# TPS54260.net
KiCad netlist of a schematic drawn in Altium Designer
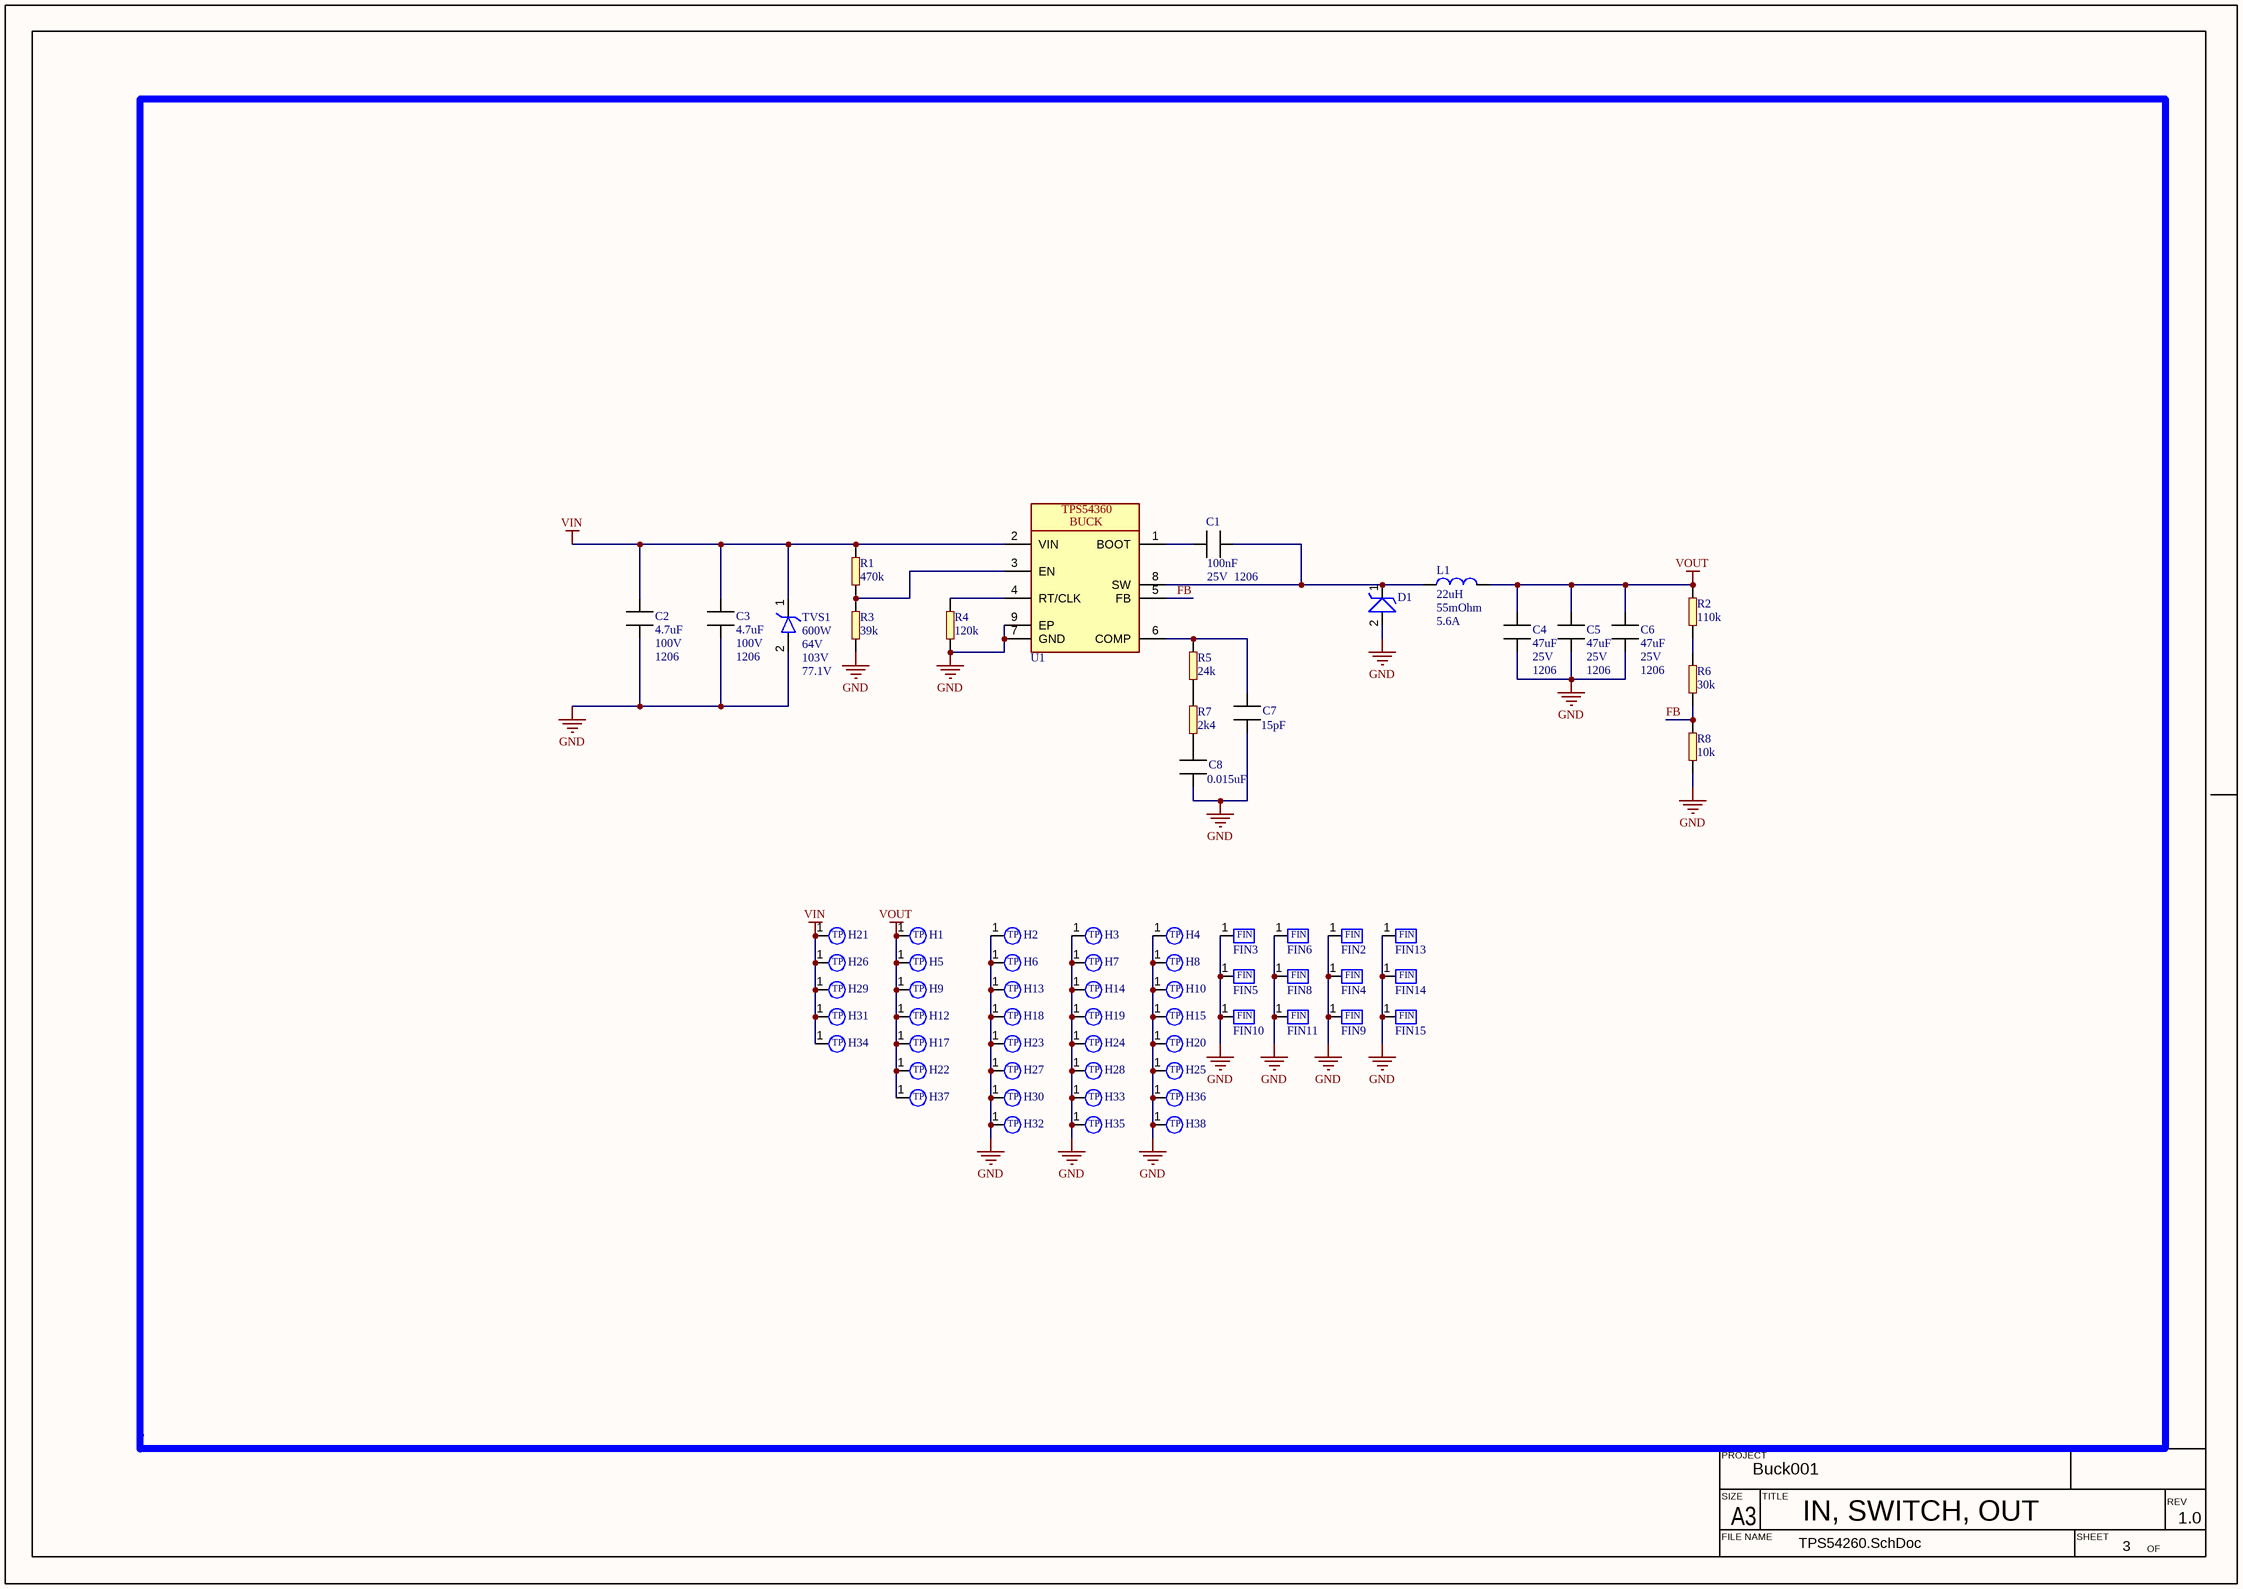
[diagram p0: TPS54260.SchDoc]

(export (version "E")
  (design (tool "Eeschema 10.0.6"))
  (components
    (comp (ref "C1")
      (value "100nF")
      (footprint "CAP1206")
      (description "MLCC 1206 (3216 Metric)")
      (fields
        (field (name "VOLTAGE") "25V")
        (field (name "PACKAGE") "1206")
        (field (name "Comment") "MLCC_1206")
      )
      (libsource (lib "Capacitor") (part "MLCC_1206"))
    )
    (comp (ref "C2")
      (value "4.7uF")
      (footprint "CAP1206")
      (description "MLCC 1206 (3216 Metric)")
      (fields
        (field (name "VOLTAGE") "100V")
        (field (name "PACKAGE") "1206")
        (field (name "Comment") "MLCC_1206")
      )
      (libsource (lib "Capacitor") (part "MLCC_1206"))
    )
    (comp (ref "C3")
      (value "4.7uF")
      (footprint "CAP1206")
      (description "MLCC 1206 (3216 Metric)")
      (fields
        (field (name "VOLTAGE") "100V")
        (field (name "PACKAGE") "1206")
        (field (name "Comment") "MLCC_1206")
      )
      (libsource (lib "Capacitor") (part "MLCC_1206"))
    )
    (comp (ref "C4")
      (value "47uF")
      (footprint "CAP1206")
      (description "MLCC 1206 (3216 Metric)")
      (fields
        (field (name "VOLTAGE") "25V")
        (field (name "PACKAGE") "1206")
        (field (name "Comment") "MLCC_1206")
      )
      (libsource (lib "Capacitor") (part "MLCC_1206"))
    )
    (comp (ref "C5")
      (value "47uF")
      (footprint "CAP1206")
      (description "MLCC 1206 (3216 Metric)")
      (fields
        (field (name "VOLTAGE") "25V")
        (field (name "PACKAGE") "1206")
        (field (name "Comment") "MLCC_1206")
      )
      (libsource (lib "Capacitor") (part "MLCC_1206"))
    )
    (comp (ref "C6")
      (value "47uF")
      (footprint "CAP1206")
      (description "MLCC 1206 (3216 Metric)")
      (fields
        (field (name "VOLTAGE") "25V")
        (field (name "PACKAGE") "1206")
        (field (name "Comment") "MLCC_1206")
      )
      (libsource (lib "Capacitor") (part "MLCC_1206"))
    )
    (comp (ref "C7")
      (value "15pF")
      (footprint "CAPC1608X10N")
      (description "Chip Capacitor, 2-Leads, Body 1.60x0.80mm, IPC Medium Density")
      (fields (field (name "Comment") "ERP_102-1"))
      (libsource (lib "Capacitor") (part "MLCC_0603"))
    )
    (comp (ref "C8")
      (value "0.015uF")
      (footprint "CAPC1608X10N")
      (description "Chip Capacitor, 2-Leads, Body 1.60x0.80mm, IPC Medium Density")
      (fields (field (name "Comment") "ERP_102-1"))
      (libsource (lib "Capacitor") (part "MLCC_0603"))
    )
    (comp (ref "D1")
      (value "CDBB_5XX_HF")
      (footprint "SMB(DO214AA)")
      (description "SMB(DO-214AA) DIODE HF 5A")
      (libsource (lib "Schottky") (part "CDBB_5XX_HF"))
    )
    (comp (ref "FIN2")
      (value "FIN_5X1")
      (footprint "FIN_5X1")
      (description "FIN_5X1 Radiator")
      (libsource (lib "Jumper") (part "FIN_5X1"))
    )
    (comp (ref "FIN3")
      (value "FIN_5X1")
      (footprint "FIN_5X1")
      (description "FIN_5X1 Radiator")
      (libsource (lib "Jumper") (part "FIN_5X1"))
    )
    (comp (ref "FIN4")
      (value "FIN_5X1")
      (footprint "FIN_5X1")
      (description "FIN_5X1 Radiator")
      (libsource (lib "Jumper") (part "FIN_5X1"))
    )
    (comp (ref "FIN5")
      (value "FIN_5X1")
      (footprint "FIN_5X1")
      (description "FIN_5X1 Radiator")
      (libsource (lib "Jumper") (part "FIN_5X1"))
    )
    (comp (ref "FIN6")
      (value "FIN_5X1")
      (footprint "FIN_5X1")
      (description "FIN_5X1 Radiator")
      (libsource (lib "Jumper") (part "FIN_5X1"))
    )
    (comp (ref "FIN8")
      (value "FIN_5X1")
      (footprint "FIN_5X1")
      (description "FIN_5X1 Radiator")
      (libsource (lib "Jumper") (part "FIN_5X1"))
    )
    (comp (ref "FIN9")
      (value "FIN_5X1")
      (footprint "FIN_5X1")
      (description "FIN_5X1 Radiator")
      (libsource (lib "Jumper") (part "FIN_5X1"))
    )
    (comp (ref "FIN10")
      (value "FIN_5X1")
      (footprint "FIN_5X1")
      (description "FIN_5X1 Radiator")
      (libsource (lib "Jumper") (part "FIN_5X1"))
    )
    (comp (ref "FIN11")
      (value "FIN_5X1")
      (footprint "FIN_5X1")
      (description "FIN_5X1 Radiator")
      (libsource (lib "Jumper") (part "FIN_5X1"))
    )
    (comp (ref "FIN13")
      (value "FIN_5X1")
      (footprint "FIN_5X1")
      (description "FIN_5X1 Radiator")
      (libsource (lib "Jumper") (part "FIN_5X1"))
    )
    (comp (ref "FIN14")
      (value "FIN_5X1")
      (footprint "FIN_5X1")
      (description "FIN_5X1 Radiator")
      (libsource (lib "Jumper") (part "FIN_5X1"))
    )
    (comp (ref "FIN15")
      (value "FIN_5X1")
      (footprint "FIN_5X1")
      (description "FIN_5X1 Radiator")
      (libsource (lib "Jumper") (part "FIN_5X1"))
    )
    (comp (ref "H1")
      (value "Castalated_Hole_1MM")
      (footprint "CS_1MM")
      (libsource (lib "Jumper") (part "Castalated_Hole_1MM"))
    )
    (comp (ref "H2")
      (value "Castalated_Hole_1MM")
      (footprint "CS_1MM")
      (libsource (lib "Jumper") (part "Castalated_Hole_1MM"))
    )
    (comp (ref "H3")
      (value "Castalated_Hole_1MM")
      (footprint "CS_1MM")
      (libsource (lib "Jumper") (part "Castalated_Hole_1MM"))
    )
    (comp (ref "H4")
      (value "Castalated_Hole_1MM")
      (footprint "CS_1MM")
      (libsource (lib "Jumper") (part "Castalated_Hole_1MM"))
    )
    (comp (ref "H5")
      (value "Castalated_Hole_1MM")
      (footprint "CS_1MM")
      (libsource (lib "Jumper") (part "Castalated_Hole_1MM"))
    )
    (comp (ref "H6")
      (value "Castalated_Hole_1MM")
      (footprint "CS_1MM")
      (libsource (lib "Jumper") (part "Castalated_Hole_1MM"))
    )
    (comp (ref "H7")
      (value "Castalated_Hole_1MM")
      (footprint "CS_1MM")
      (libsource (lib "Jumper") (part "Castalated_Hole_1MM"))
    )
    (comp (ref "H8")
      (value "Castalated_Hole_1MM")
      (footprint "CS_1MM")
      (libsource (lib "Jumper") (part "Castalated_Hole_1MM"))
    )
    (comp (ref "H9")
      (value "Castalated_Hole_1MM")
      (footprint "CS_1MM")
      (libsource (lib "Jumper") (part "Castalated_Hole_1MM"))
    )
    (comp (ref "H10")
      (value "Castalated_Hole_1MM")
      (footprint "CS_1MM")
      (libsource (lib "Jumper") (part "Castalated_Hole_1MM"))
    )
    (comp (ref "H12")
      (value "Castalated_Hole_1MM")
      (footprint "CS_1MM")
      (libsource (lib "Jumper") (part "Castalated_Hole_1MM"))
    )
    (comp (ref "H13")
      (value "Castalated_Hole_1MM")
      (footprint "CS_1MM")
      (libsource (lib "Jumper") (part "Castalated_Hole_1MM"))
    )
    (comp (ref "H14")
      (value "Castalated_Hole_1MM")
      (footprint "CS_1MM")
      (libsource (lib "Jumper") (part "Castalated_Hole_1MM"))
    )
    (comp (ref "H15")
      (value "Castalated_Hole_1MM")
      (footprint "CS_1MM")
      (libsource (lib "Jumper") (part "Castalated_Hole_1MM"))
    )
    (comp (ref "H17")
      (value "Castalated_Hole_1MM")
      (footprint "CS_1MM")
      (libsource (lib "Jumper") (part "Castalated_Hole_1MM"))
    )
    (comp (ref "H18")
      (value "Castalated_Hole_1MM")
      (footprint "CS_1MM")
      (libsource (lib "Jumper") (part "Castalated_Hole_1MM"))
    )
    (comp (ref "H19")
      (value "Castalated_Hole_1MM")
      (footprint "CS_1MM")
      (libsource (lib "Jumper") (part "Castalated_Hole_1MM"))
    )
    (comp (ref "H20")
      (value "Castalated_Hole_1MM")
      (footprint "CS_1MM")
      (libsource (lib "Jumper") (part "Castalated_Hole_1MM"))
    )
    (comp (ref "H21")
      (value "Castalated_Hole_1MM")
      (footprint "CS_1MM")
      (libsource (lib "Jumper") (part "Castalated_Hole_1MM"))
    )
    (comp (ref "H22")
      (value "Castalated_Hole_1MM")
      (footprint "CS_1MM")
      (libsource (lib "Jumper") (part "Castalated_Hole_1MM"))
    )
    (comp (ref "H23")
      (value "Castalated_Hole_1MM")
      (footprint "CS_1MM")
      (libsource (lib "Jumper") (part "Castalated_Hole_1MM"))
    )
    (comp (ref "H24")
      (value "Castalated_Hole_1MM")
      (footprint "CS_1MM")
      (libsource (lib "Jumper") (part "Castalated_Hole_1MM"))
    )
    (comp (ref "H25")
      (value "Castalated_Hole_1MM")
      (footprint "CS_1MM")
      (libsource (lib "Jumper") (part "Castalated_Hole_1MM"))
    )
    (comp (ref "H26")
      (value "Castalated_Hole_1MM")
      (footprint "CS_1MM")
      (libsource (lib "Jumper") (part "Castalated_Hole_1MM"))
    )
    (comp (ref "H27")
      (value "Castalated_Hole_1MM")
      (footprint "CS_1MM")
      (libsource (lib "Jumper") (part "Castalated_Hole_1MM"))
    )
    (comp (ref "H28")
      (value "Castalated_Hole_1MM")
      (footprint "CS_1MM")
      (libsource (lib "Jumper") (part "Castalated_Hole_1MM"))
    )
    (comp (ref "H29")
      (value "Castalated_Hole_1MM")
      (footprint "CS_1MM")
      (libsource (lib "Jumper") (part "Castalated_Hole_1MM"))
    )
    (comp (ref "H30")
      (value "Castalated_Hole_1MM")
      (footprint "CS_1MM")
      (libsource (lib "Jumper") (part "Castalated_Hole_1MM"))
    )
    (comp (ref "H31")
      (value "Castalated_Hole_1MM")
      (footprint "CS_1MM")
      (libsource (lib "Jumper") (part "Castalated_Hole_1MM"))
    )
    (comp (ref "H32")
      (value "Castalated_Hole_1MM")
      (footprint "CS_1MM")
      (libsource (lib "Jumper") (part "Castalated_Hole_1MM"))
    )
    (comp (ref "H33")
      (value "Castalated_Hole_1MM")
      (footprint "CS_1MM")
      (libsource (lib "Jumper") (part "Castalated_Hole_1MM"))
    )
    (comp (ref "H34")
      (value "Castalated_Hole_1MM")
      (footprint "CS_1MM")
      (libsource (lib "Jumper") (part "Castalated_Hole_1MM"))
    )
    (comp (ref "H35")
      (value "Castalated_Hole_1MM")
      (footprint "CS_1MM")
      (libsource (lib "Jumper") (part "Castalated_Hole_1MM"))
    )
    (comp (ref "H36")
      (value "Castalated_Hole_1MM")
      (footprint "CS_1MM")
      (libsource (lib "Jumper") (part "Castalated_Hole_1MM"))
    )
    (comp (ref "H37")
      (value "Castalated_Hole_1MM")
      (footprint "CS_1MM")
      (libsource (lib "Jumper") (part "Castalated_Hole_1MM"))
    )
    (comp (ref "H38")
      (value "Castalated_Hole_1MM")
      (footprint "CS_1MM")
      (libsource (lib "Jumper") (part "Castalated_Hole_1MM"))
    )
    (comp (ref "L1")
      (value "22uH")
      (footprint "SRP6060FA")
      (description "SRP6060FA Bourns 6.4 x 6.6 MM")
      (fields (field (name "DCR") "55mOhm") (field (name "ISAT") "5.6A") (field (name "Comment") "SRP6060FA"))
      (libsource (lib "Inductor") (part "SRP6060FA"))
    )
    (comp (ref "R1")
      (value "470k")
      (footprint "RES_0603")
      (description "RES_0603")
      (fields (field (name "Comment") "ERP_101-1"))
      (libsource (lib "Resistor") (part "RES_0603"))
    )
    (comp (ref "R2")
      (value "110k")
      (footprint "RES_0603")
      (description "RES_0603")
      (fields (field (name "Comment") "ERP_101-1"))
      (libsource (lib "Resistor") (part "RES_0603"))
    )
    (comp (ref "R3")
      (value "39k")
      (footprint "RES_0603")
      (description "RES_0603")
      (fields (field (name "Comment") "ERP_101-1"))
      (libsource (lib "Resistor") (part "RES_0603"))
    )
    (comp (ref "R4")
      (value "120k")
      (footprint "RES_0603")
      (description "RES_0603")
      (fields (field (name "Comment") "ERP_101-1"))
      (libsource (lib "Resistor") (part "RES_0603"))
    )
    (comp (ref "R5")
      (value "24k")
      (footprint "RES_0603")
      (description "RES_0603")
      (fields (field (name "Comment") "ERP_101-1"))
      (libsource (lib "Resistor") (part "RES_0603"))
    )
    (comp (ref "R6")
      (value "30k")
      (footprint "RES_0603")
      (description "RES_0603")
      (fields (field (name "Comment") "ERP_101-1"))
      (libsource (lib "Resistor") (part "RES_0603"))
    )
    (comp (ref "R7")
      (value "2k4")
      (footprint "RES_0603")
      (description "RES_0603")
      (fields (field (name "Comment") "ERP_101-1"))
      (libsource (lib "Resistor") (part "RES_0603"))
    )
    (comp (ref "R8")
      (value "10k")
      (footprint "RES_0603")
      (description "RES_0603")
      (fields (field (name "Comment") "ERP_101-1"))
      (libsource (lib "Resistor") (part "RES_0603"))
    )
    (comp (ref "TVS1")
      (value "SMBJ58A")
      (footprint "SMBJ58A")
      (description "TVS DIODE DO-214AA, SMB")
      (fields
        (field (name "PD") "600W")
        (field (name "VRV") "64V")
        (field (name "VCL") "103V")
        (field (name "VBR") "77.1V")
      )
      (libsource (lib "TVS") (part "SMBJ58A"))
    )
    (comp (ref "U1")
      (value "TPS54360DDAR")
      (footprint "TPS54360DDAR")
      (libsource (lib "DCDC_Switcher") (part "TPS54360DDAR"))
    )
  )
  (nets
    (net (code "1") (name "/FB") (class "Default")
      (node (ref "R6") (pin "1") (pinfunction "1_1") (pintype "passive"))
      (node (ref "R8") (pin "2") (pinfunction "2_2") (pintype "passive"))
      (node (ref "U1") (pin "5") (pinfunction "FB_5") (pintype "passive"))
    )
    (net (code "2") (name "GND") (class "Default")
      (node (ref "C2") (pin "2") (pinfunction "2_2") (pintype "passive"))
      (node (ref "C3") (pin "2") (pinfunction "2_2") (pintype "passive"))
      (node (ref "C4") (pin "2") (pinfunction "2_2") (pintype "passive"))
      (node (ref "C5") (pin "2") (pinfunction "2_2") (pintype "passive"))
      (node (ref "C6") (pin "2") (pinfunction "2_2") (pintype "passive"))
      (node (ref "C7") (pin "2") (pinfunction "2_2") (pintype "passive"))
      (node (ref "C8") (pin "2") (pinfunction "2_2") (pintype "passive"))
      (node (ref "D1") (pin "2") (pinfunction "A_2") (pintype "passive"))
      (node (ref "FIN10") (pin "1") (pinfunction "1_1") (pintype "passive"))
      (node (ref "FIN11") (pin "1") (pinfunction "1_1") (pintype "passive"))
      (node (ref "FIN13") (pin "1") (pinfunction "1_1") (pintype "passive"))
      (node (ref "FIN14") (pin "1") (pinfunction "1_1") (pintype "passive"))
      (node (ref "FIN15") (pin "1") (pinfunction "1_1") (pintype "passive"))
      (node (ref "FIN2") (pin "1") (pinfunction "1_1") (pintype "passive"))
      (node (ref "FIN3") (pin "1") (pinfunction "1_1") (pintype "passive"))
      (node (ref "FIN4") (pin "1") (pinfunction "1_1") (pintype "passive"))
      (node (ref "FIN5") (pin "1") (pinfunction "1_1") (pintype "passive"))
      (node (ref "FIN6") (pin "1") (pinfunction "1_1") (pintype "passive"))
      (node (ref "FIN8") (pin "1") (pinfunction "1_1") (pintype "passive"))
      (node (ref "FIN9") (pin "1") (pinfunction "1_1") (pintype "passive"))
      (node (ref "H10") (pin "1") (pinfunction "1_1") (pintype "passive"))
      (node (ref "H13") (pin "1") (pinfunction "1_1") (pintype "passive"))
      (node (ref "H14") (pin "1") (pinfunction "1_1") (pintype "passive"))
      (node (ref "H15") (pin "1") (pinfunction "1_1") (pintype "passive"))
      (node (ref "H18") (pin "1") (pinfunction "1_1") (pintype "passive"))
      (node (ref "H19") (pin "1") (pinfunction "1_1") (pintype "passive"))
      (node (ref "H2") (pin "1") (pinfunction "1_1") (pintype "passive"))
      (node (ref "H20") (pin "1") (pinfunction "1_1") (pintype "passive"))
      (node (ref "H23") (pin "1") (pinfunction "1_1") (pintype "passive"))
      (node (ref "H24") (pin "1") (pinfunction "1_1") (pintype "passive"))
      (node (ref "H25") (pin "1") (pinfunction "1_1") (pintype "passive"))
      (node (ref "H27") (pin "1") (pinfunction "1_1") (pintype "passive"))
      (node (ref "H28") (pin "1") (pinfunction "1_1") (pintype "passive"))
      (node (ref "H3") (pin "1") (pinfunction "1_1") (pintype "passive"))
      (node (ref "H30") (pin "1") (pinfunction "1_1") (pintype "passive"))
      (node (ref "H32") (pin "1") (pinfunction "1_1") (pintype "passive"))
      (node (ref "H33") (pin "1") (pinfunction "1_1") (pintype "passive"))
      (node (ref "H35") (pin "1") (pinfunction "1_1") (pintype "passive"))
      (node (ref "H36") (pin "1") (pinfunction "1_1") (pintype "passive"))
      (node (ref "H38") (pin "1") (pinfunction "1_1") (pintype "passive"))
      (node (ref "H4") (pin "1") (pinfunction "1_1") (pintype "passive"))
      (node (ref "H6") (pin "1") (pinfunction "1_1") (pintype "passive"))
      (node (ref "H7") (pin "1") (pinfunction "1_1") (pintype "passive"))
      (node (ref "H8") (pin "1") (pinfunction "1_1") (pintype "passive"))
      (node (ref "R3") (pin "1") (pinfunction "1_1") (pintype "passive"))
      (node (ref "R4") (pin "1") (pinfunction "1_1") (pintype "passive"))
      (node (ref "R8") (pin "1") (pinfunction "1_1") (pintype "passive"))
      (node (ref "TVS1") (pin "2") (pinfunction "A_2") (pintype "passive"))
      (node (ref "U1") (pin "7") (pinfunction "GND_7") (pintype "passive"))
      (node (ref "U1") (pin "9") (pinfunction "EP_9") (pintype "passive"))
    )
    (net (code "3") (name "Net-(C8-Pad1)") (class "Default")
      (node (ref "C8") (pin "1") (pinfunction "1_1") (pintype "passive"))
      (node (ref "R7") (pin "1") (pinfunction "1_1") (pintype "passive"))
    )
    (net (code "4") (name "Net-(D1-K)") (class "Default")
      (node (ref "C1") (pin "2") (pinfunction "2_2") (pintype "passive"))
      (node (ref "D1") (pin "1") (pinfunction "K_1") (pintype "passive"))
      (node (ref "L1") (pin "1") (pinfunction "1_1") (pintype "passive"))
      (node (ref "U1") (pin "8") (pinfunction "SW_8") (pintype "passive"))
    )
    (net (code "5") (name "Net-(R2-Pad1)") (class "Default")
      (node (ref "R2") (pin "1") (pinfunction "1_1") (pintype "passive"))
      (node (ref "R6") (pin "2") (pinfunction "2_2") (pintype "passive"))
    )
    (net (code "6") (name "Net-(R5-Pad1)") (class "Default")
      (node (ref "R5") (pin "1") (pinfunction "1_1") (pintype "passive"))
      (node (ref "R7") (pin "2") (pinfunction "2_2") (pintype "passive"))
    )
    (net (code "7") (name "Net-(U1-BOOT)") (class "Default")
      (node (ref "C1") (pin "1") (pinfunction "1_1") (pintype "passive"))
      (node (ref "U1") (pin "1") (pinfunction "BOOT_1") (pintype "passive"))
    )
    (net (code "8") (name "Net-(U1-COMP)") (class "Default")
      (node (ref "C7") (pin "1") (pinfunction "1_1") (pintype "passive"))
      (node (ref "R5") (pin "2") (pinfunction "2_2") (pintype "passive"))
      (node (ref "U1") (pin "6") (pinfunction "COMP_6") (pintype "passive"))
    )
    (net (code "9") (name "Net-(U1-EN)") (class "Default")
      (node (ref "R1") (pin "1") (pinfunction "1_1") (pintype "passive"))
      (node (ref "R3") (pin "2") (pinfunction "2_2") (pintype "passive"))
      (node (ref "U1") (pin "3") (pinfunction "EN_3") (pintype "passive"))
    )
    (net (code "10") (name "Net-(U1-RT{slash}CLK)") (class "Default")
      (node (ref "R4") (pin "2") (pinfunction "2_2") (pintype "passive"))
      (node (ref "U1") (pin "4") (pinfunction "RT/CLK_4") (pintype "passive"))
    )
    (net (code "11") (name "VIN") (class "Default")
      (node (ref "C2") (pin "1") (pinfunction "1_1") (pintype "passive"))
      (node (ref "C3") (pin "1") (pinfunction "1_1") (pintype "passive"))
      (node (ref "H21") (pin "1") (pinfunction "1_1") (pintype "passive"))
      (node (ref "H26") (pin "1") (pinfunction "1_1") (pintype "passive"))
      (node (ref "H29") (pin "1") (pinfunction "1_1") (pintype "passive"))
      (node (ref "H31") (pin "1") (pinfunction "1_1") (pintype "passive"))
      (node (ref "H34") (pin "1") (pinfunction "1_1") (pintype "passive"))
      (node (ref "R1") (pin "2") (pinfunction "2_2") (pintype "passive"))
      (node (ref "TVS1") (pin "1") (pinfunction "K_1") (pintype "passive"))
      (node (ref "U1") (pin "2") (pinfunction "VIN_2") (pintype "passive"))
    )
    (net (code "12") (name "VOUT") (class "Default")
      (node (ref "C4") (pin "1") (pinfunction "1_1") (pintype "passive"))
      (node (ref "C5") (pin "1") (pinfunction "1_1") (pintype "passive"))
      (node (ref "C6") (pin "1") (pinfunction "1_1") (pintype "passive"))
      (node (ref "H1") (pin "1") (pinfunction "1_1") (pintype "passive"))
      (node (ref "H12") (pin "1") (pinfunction "1_1") (pintype "passive"))
      (node (ref "H17") (pin "1") (pinfunction "1_1") (pintype "passive"))
      (node (ref "H22") (pin "1") (pinfunction "1_1") (pintype "passive"))
      (node (ref "H37") (pin "1") (pinfunction "1_1") (pintype "passive"))
      (node (ref "H5") (pin "1") (pinfunction "1_1") (pintype "passive"))
      (node (ref "H9") (pin "1") (pinfunction "1_1") (pintype "passive"))
      (node (ref "L1") (pin "2") (pinfunction "2_2") (pintype "passive"))
      (node (ref "R2") (pin "2") (pinfunction "2_2") (pintype "passive"))
    )
  )
)
